# moduloSensores.net
KiCad netlist of a schematic drawn in EAGLE
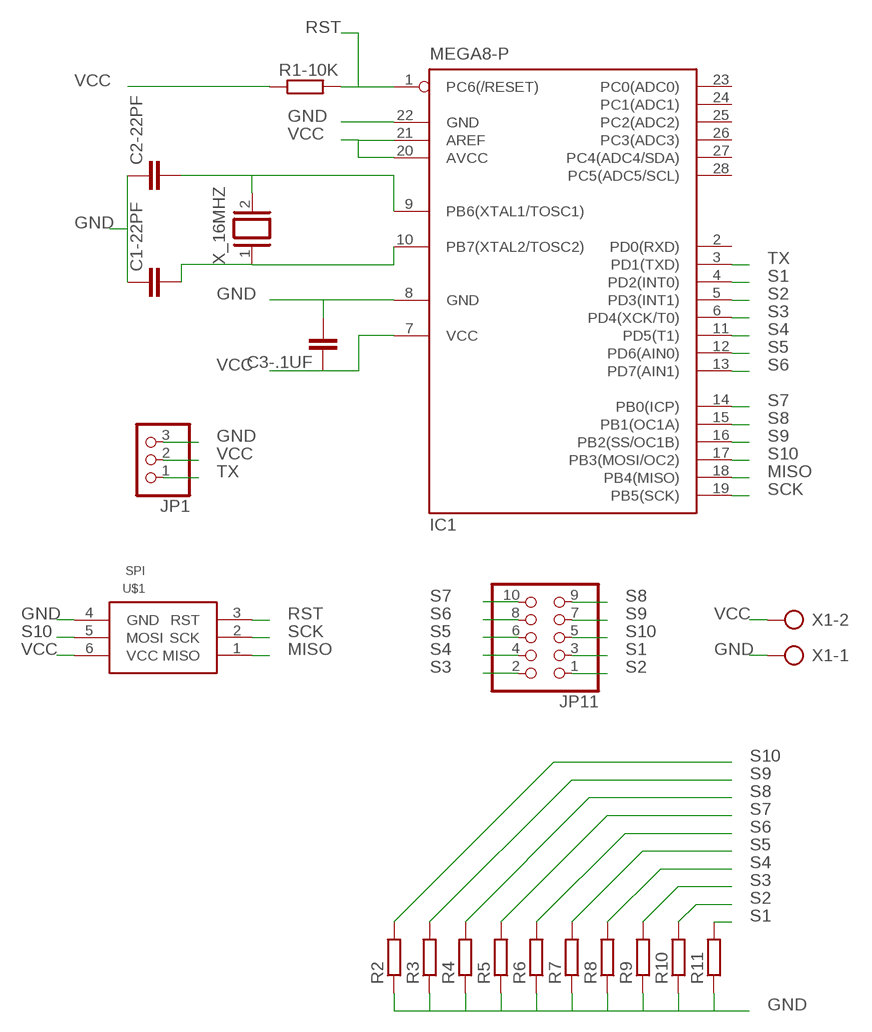
[diagram p0: schematic, sheet 1]

(export (version "E")
  (design (tool "Eeschema 10.0.6"))
  (components
    (comp (ref "C1-22PF")
      (value "C-EU050-025X075")
      (footprint "eagle-import:C050-025X075")
      (libsource (lib "eagle-import") (part "C-EU050-025X075"))
    )
    (comp (ref "C2-22PF")
      (value "C-EU050-025X075")
      (footprint "eagle-import:C050-025X075")
      (libsource (lib "eagle-import") (part "C-EU050-025X075"))
    )
    (comp (ref "C3-.1UF")
      (value "C-EU050-025X075")
      (footprint "eagle-import:C050-025X075")
      (libsource (lib "eagle-import") (part "C-EU050-025X075"))
    )
    (comp (ref "IC1")
      (value "MEGA8-P")
      (footprint "eagle-import:DIL28-3")
      (libsource (lib "eagle-import") (part "MEGA8-P"))
    )
    (comp (ref "JP1")
      (value "PINHD-1X3")
      (footprint "eagle-import:1X03")
      (libsource (lib "eagle-import") (part "PINHD-1X3"))
    )
    (comp (ref "JP11")
      (value "PINHD-2X5")
      (footprint "eagle-import:2X05")
      (libsource (lib "eagle-import") (part "PINHD-2X5"))
    )
    (comp (ref "R1-10K")
      (value "R-EU_0204/7")
      (footprint "eagle-import:0204_7")
      (libsource (lib "eagle-import") (part "R-EU_0204/7"))
    )
    (comp (ref "R2")
      (value "R-EU_0204/7")
      (footprint "eagle-import:0204_7")
      (libsource (lib "eagle-import") (part "R-EU_0204/7"))
    )
    (comp (ref "R3")
      (value "R-EU_0204/7")
      (footprint "eagle-import:0204_7")
      (libsource (lib "eagle-import") (part "R-EU_0204/7"))
    )
    (comp (ref "R4")
      (value "R-EU_0204/7")
      (footprint "eagle-import:0204_7")
      (libsource (lib "eagle-import") (part "R-EU_0204/7"))
    )
    (comp (ref "R5")
      (value "R-EU_0204/7")
      (footprint "eagle-import:0204_7")
      (libsource (lib "eagle-import") (part "R-EU_0204/7"))
    )
    (comp (ref "R6")
      (value "R-EU_0204/7")
      (footprint "eagle-import:0204_7")
      (libsource (lib "eagle-import") (part "R-EU_0204/7"))
    )
    (comp (ref "R7")
      (value "R-EU_0204/7")
      (footprint "eagle-import:0204_7")
      (libsource (lib "eagle-import") (part "R-EU_0204/7"))
    )
    (comp (ref "R8")
      (value "R-EU_0204/7")
      (footprint "eagle-import:0204_7")
      (libsource (lib "eagle-import") (part "R-EU_0204/7"))
    )
    (comp (ref "R9")
      (value "R-EU_0204/7")
      (footprint "eagle-import:0204_7")
      (libsource (lib "eagle-import") (part "R-EU_0204/7"))
    )
    (comp (ref "R10")
      (value "R-EU_0204/7")
      (footprint "eagle-import:0204_7")
      (libsource (lib "eagle-import") (part "R-EU_0204/7"))
    )
    (comp (ref "R11")
      (value "R-EU_0204/7")
      (footprint "eagle-import:0204_7")
      (libsource (lib "eagle-import") (part "R-EU_0204/7"))
    )
    (comp (ref "U$1")
      (value "SPI")
      (footprint "eagle-import:HEAD-2X3")
      (libsource (lib "eagle-import") (part "SPI"))
    )
    (comp (ref "X1")
      (value "AK500/2")
      (footprint "eagle-import:AK500_2")
      (libsource (lib "eagle-import") (part "AK500/2"))
    )
    (comp (ref "X_16MHZ")
      (value "XTAL/S")
      (footprint "eagle-import:QS")
      (libsource (lib "eagle-import") (part "XTAL/S"))
    )
  )
  (nets
    (net (code "1") (name "/GND") (class "Default")
      (node (ref "C1-22PF") (pin "1") (pinfunction "1_1") (pintype "passive"))
      (node (ref "C2-22PF") (pin "1") (pinfunction "1_1") (pintype "passive"))
      (node (ref "C3-.1UF") (pin "2") (pinfunction "2_2") (pintype "passive"))
      (node (ref "IC1") (pin "22") (pinfunction "GND_22") (pintype "power_in"))
      (node (ref "IC1") (pin "8") (pinfunction "GND_8") (pintype "power_in"))
      (node (ref "JP1") (pin "3") (pinfunction "3_3") (pintype "passive"))
      (node (ref "R10") (pin "1") (pinfunction "1_1") (pintype "passive"))
      (node (ref "R11") (pin "1") (pinfunction "1_1") (pintype "passive"))
      (node (ref "R2") (pin "1") (pinfunction "1_1") (pintype "passive"))
      (node (ref "R3") (pin "1") (pinfunction "1_1") (pintype "passive"))
      (node (ref "R4") (pin "1") (pinfunction "1_1") (pintype "passive"))
      (node (ref "R5") (pin "1") (pinfunction "1_1") (pintype "passive"))
      (node (ref "R6") (pin "1") (pinfunction "1_1") (pintype "passive"))
      (node (ref "R7") (pin "1") (pinfunction "1_1") (pintype "passive"))
      (node (ref "R8") (pin "1") (pinfunction "1_1") (pintype "passive"))
      (node (ref "R9") (pin "1") (pinfunction "1_1") (pintype "passive"))
      (node (ref "U$1") (pin "4") (pinfunction "GND_4") (pintype "bidirectional"))
      (node (ref "X1") (pin "1") (pinfunction "KL_1") (pintype "passive"))
    )
    (net (code "2") (name "/MISO") (class "Default")
      (node (ref "IC1") (pin "18") (pinfunction "PB4(MISO)_18") (pintype "bidirectional"))
      (node (ref "U$1") (pin "1") (pinfunction "MISO_1") (pintype "bidirectional"))
    )
    (net (code "3") (name "/RST") (class "Default")
      (node (ref "IC1") (pin "1") (pinfunction "PC6(/RESET)_1") (pintype "bidirectional"))
      (node (ref "R1-10K") (pin "2") (pinfunction "2_2") (pintype "passive"))
      (node (ref "U$1") (pin "3") (pinfunction "RST_3") (pintype "bidirectional"))
    )
    (net (code "4") (name "/S1") (class "Default")
      (node (ref "IC1") (pin "4") (pinfunction "PD2(INT0)_4") (pintype "bidirectional"))
      (node (ref "JP11") (pin "3") (pinfunction "3_3") (pintype "passive"))
      (node (ref "R11") (pin "2") (pinfunction "2_2") (pintype "passive"))
    )
    (net (code "5") (name "/S2") (class "Default")
      (node (ref "IC1") (pin "5") (pinfunction "PD3(INT1)_5") (pintype "bidirectional"))
      (node (ref "JP11") (pin "1") (pinfunction "1_1") (pintype "passive"))
      (node (ref "R10") (pin "2") (pinfunction "2_2") (pintype "passive"))
    )
    (net (code "6") (name "/S3") (class "Default")
      (node (ref "IC1") (pin "6") (pinfunction "PD4(XCK/T0)_6") (pintype "bidirectional"))
      (node (ref "JP11") (pin "2") (pinfunction "2_2") (pintype "passive"))
      (node (ref "R9") (pin "2") (pinfunction "2_2") (pintype "passive"))
    )
    (net (code "7") (name "/S4") (class "Default")
      (node (ref "IC1") (pin "11") (pinfunction "PD5(T1)_11") (pintype "bidirectional"))
      (node (ref "JP11") (pin "4") (pinfunction "4_4") (pintype "passive"))
      (node (ref "R8") (pin "2") (pinfunction "2_2") (pintype "passive"))
    )
    (net (code "8") (name "/S5") (class "Default")
      (node (ref "IC1") (pin "12") (pinfunction "PD6(AIN0)_12") (pintype "bidirectional"))
      (node (ref "JP11") (pin "6") (pinfunction "6_6") (pintype "passive"))
      (node (ref "R7") (pin "2") (pinfunction "2_2") (pintype "passive"))
    )
    (net (code "9") (name "/S6") (class "Default")
      (node (ref "IC1") (pin "13") (pinfunction "PD7(AIN1)_13") (pintype "bidirectional"))
      (node (ref "JP11") (pin "8") (pinfunction "8_8") (pintype "passive"))
      (node (ref "R6") (pin "2") (pinfunction "2_2") (pintype "passive"))
    )
    (net (code "10") (name "/S7") (class "Default")
      (node (ref "IC1") (pin "14") (pinfunction "PB0(ICP)_14") (pintype "bidirectional"))
      (node (ref "JP11") (pin "10") (pinfunction "10_10") (pintype "passive"))
      (node (ref "R5") (pin "2") (pinfunction "2_2") (pintype "passive"))
    )
    (net (code "11") (name "/S8") (class "Default")
      (node (ref "IC1") (pin "15") (pinfunction "PB1(OC1A)_15") (pintype "bidirectional"))
      (node (ref "JP11") (pin "9") (pinfunction "9_9") (pintype "passive"))
      (node (ref "R4") (pin "2") (pinfunction "2_2") (pintype "passive"))
    )
    (net (code "12") (name "/S9") (class "Default")
      (node (ref "IC1") (pin "16") (pinfunction "PB2(SS/OC1B)_16") (pintype "bidirectional"))
      (node (ref "JP11") (pin "7") (pinfunction "7_7") (pintype "passive"))
      (node (ref "R3") (pin "2") (pinfunction "2_2") (pintype "passive"))
    )
    (net (code "13") (name "/S10") (class "Default")
      (node (ref "IC1") (pin "17") (pinfunction "PB3(MOSI/OC2)_17") (pintype "bidirectional"))
      (node (ref "JP11") (pin "5") (pinfunction "5_5") (pintype "passive"))
      (node (ref "R2") (pin "2") (pinfunction "2_2") (pintype "passive"))
      (node (ref "U$1") (pin "5") (pinfunction "MOSI_5") (pintype "bidirectional"))
    )
    (net (code "14") (name "/SCK") (class "Default")
      (node (ref "IC1") (pin "19") (pinfunction "PB5(SCK)_19") (pintype "bidirectional"))
      (node (ref "U$1") (pin "2") (pinfunction "SCK_2") (pintype "bidirectional"))
    )
    (net (code "15") (name "/TX") (class "Default")
      (node (ref "IC1") (pin "3") (pinfunction "PD1(TXD)_3") (pintype "bidirectional"))
      (node (ref "JP1") (pin "1") (pinfunction "1_1") (pintype "passive"))
    )
    (net (code "16") (name "/VCC") (class "Default")
      (node (ref "C3-.1UF") (pin "1") (pinfunction "1_1") (pintype "passive"))
      (node (ref "IC1") (pin "20") (pinfunction "AVCC_20") (pintype "power_in"))
      (node (ref "IC1") (pin "21") (pinfunction "AREF_21") (pintype "passive"))
      (node (ref "IC1") (pin "7") (pinfunction "VCC_7") (pintype "power_in"))
      (node (ref "JP1") (pin "2") (pinfunction "2_2") (pintype "passive"))
      (node (ref "R1-10K") (pin "1") (pinfunction "1_1") (pintype "passive"))
      (node (ref "U$1") (pin "6") (pinfunction "VCC_6") (pintype "bidirectional"))
      (node (ref "X1") (pin "2") (pinfunction "KL_2") (pintype "passive"))
    )
    (net (code "17") (name "Net-(IC1-PB6(XTAL1{slash}TOSC1))") (class "Default")
      (node (ref "C2-22PF") (pin "2") (pinfunction "2_2") (pintype "passive"))
      (node (ref "IC1") (pin "9") (pinfunction "PB6(XTAL1/TOSC1)_9") (pintype "bidirectional"))
      (node (ref "X_16MHZ") (pin "2") (pinfunction "2_2") (pintype "passive"))
    )
    (net (code "18") (name "Net-(IC1-PB7(XTAL2{slash}TOSC2))") (class "Default")
      (node (ref "C1-22PF") (pin "2") (pinfunction "2_2") (pintype "passive"))
      (node (ref "IC1") (pin "10") (pinfunction "PB7(XTAL2/TOSC2)_10") (pintype "bidirectional"))
      (node (ref "X_16MHZ") (pin "1") (pinfunction "1_1") (pintype "passive"))
    )
    (net (code "19") (name "unconnected-(IC1-PC0(ADC0)-Pad23)") (class "Default")
      (node (ref "IC1") (pin "23") (pinfunction "PC0(ADC0)_23") (pintype "bidirectional"))
    )
    (net (code "20") (name "unconnected-(IC1-PC1(ADC1)-Pad24)") (class "Default")
      (node (ref "IC1") (pin "24") (pinfunction "PC1(ADC1)_24") (pintype "bidirectional"))
    )
    (net (code "21") (name "unconnected-(IC1-PC2(ADC2)-Pad25)") (class "Default")
      (node (ref "IC1") (pin "25") (pinfunction "PC2(ADC2)_25") (pintype "bidirectional"))
    )
    (net (code "22") (name "unconnected-(IC1-PC3(ADC3)-Pad26)") (class "Default")
      (node (ref "IC1") (pin "26") (pinfunction "PC3(ADC3)_26") (pintype "bidirectional"))
    )
    (net (code "23") (name "unconnected-(IC1-PC4(ADC4{slash}SDA)-Pad27)") (class "Default")
      (node (ref "IC1") (pin "27") (pinfunction "PC4(ADC4/SDA)_27") (pintype "bidirectional"))
    )
    (net (code "24") (name "unconnected-(IC1-PC5(ADC5{slash}SCL)-Pad28)") (class "Default")
      (node (ref "IC1") (pin "28") (pinfunction "PC5(ADC5/SCL)_28") (pintype "bidirectional"))
    )
    (net (code "25") (name "unconnected-(IC1-PD0(RXD)-Pad2)") (class "Default")
      (node (ref "IC1") (pin "2") (pinfunction "PD0(RXD)_2") (pintype "bidirectional"))
    )
  )
)
